# EE209_Schematic.net
KiCad netlist of a schematic drawn in Altium Designer
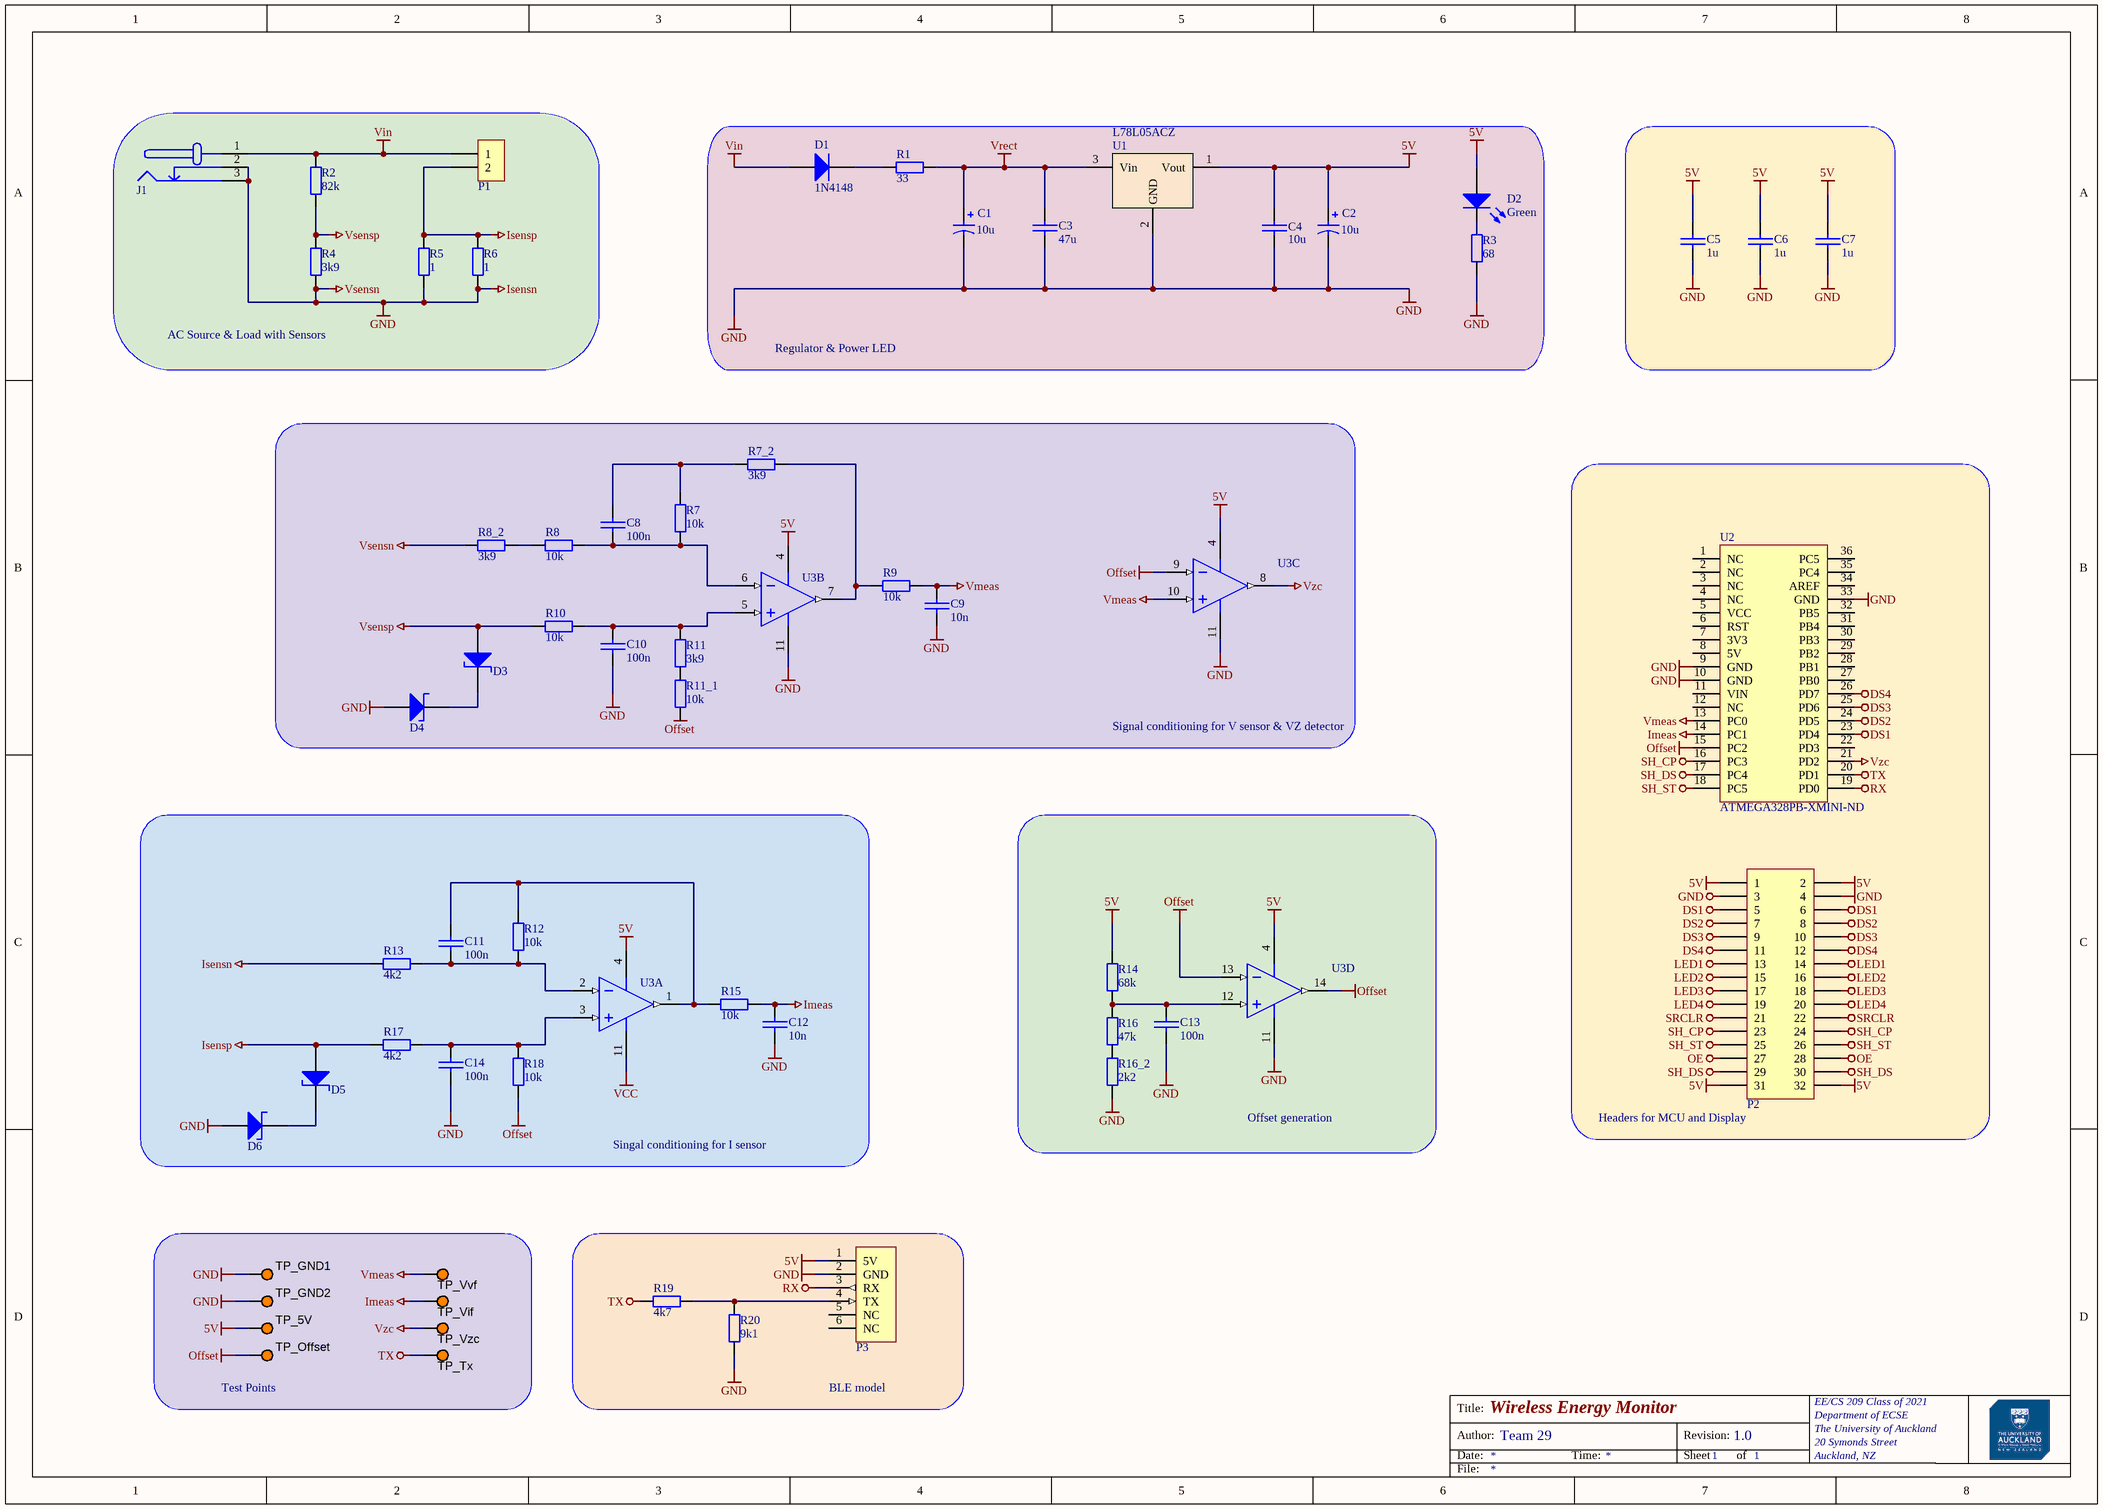
[diagram p0: EE209_Schematic.SchDoc]

(export (version "E")
  (design (tool "Eeschema 10.0.6"))
  (components
    (comp (ref "C1")
      (value "10u")
      (footprint "CAP-RAD-2.5mm Pitch")
      (description "Electrolytic capacitor with radial package, 2mm pitch and 5.2mm diameter")
      (fields (field (name "PUBLISHER") "Altium Limited"))
      (libsource (lib "EE209_Library") (part "ElecCap_TH_2P0"))
    )
    (comp (ref "C2")
      (value "10u")
      (footprint "CAP-RAD-2.5mm Pitch")
      (description "Electrolytic capacitor with radial package, 2mm pitch and 5.2mm diameter")
      (fields (field (name "PUBLISHER") "Altium Limited"))
      (libsource (lib "EE209_Library") (part "ElecCap_TH_2P0"))
    )
    (comp (ref "C3")
      (value "47u")
      (footprint "CCAP-5P0")
      (description "TH ceramic capacitor with 5mm pitch")
      (libsource (lib "EE209_Library") (part "CerCap_TH_5P0"))
    )
    (comp (ref "C4")
      (value "10u")
      (footprint "CCAP-5P0")
      (description "TH ceramic capacitor with 5mm pitch")
      (libsource (lib "EE209_Library") (part "CerCap_TH_5P0"))
    )
    (comp (ref "C5")
      (value "1u")
      (footprint "CCAP-5P0")
      (description "TH ceramic capacitor with 5mm pitch")
      (libsource (lib "EE209_Library") (part "CerCap_TH_5P0"))
    )
    (comp (ref "C6")
      (value "1u")
      (footprint "CCAP-5P0")
      (description "TH ceramic capacitor with 5mm pitch")
      (libsource (lib "EE209_Library") (part "CerCap_TH_5P0"))
    )
    (comp (ref "C7")
      (value "1u")
      (footprint "CCAP-5P0")
      (description "TH ceramic capacitor with 5mm pitch")
      (libsource (lib "EE209_Library") (part "CerCap_TH_5P0"))
    )
    (comp (ref "C8")
      (value "100n")
      (footprint "CCAP-5P0")
      (description "TH ceramic capacitor with 5mm pitch")
      (libsource (lib "EE209_Library") (part "CerCap_TH_5P0"))
    )
    (comp (ref "C9")
      (value "10n")
      (footprint "CCAP-5P0")
      (description "TH ceramic capacitor with 5mm pitch")
      (libsource (lib "EE209_Library") (part "CerCap_TH_5P0"))
    )
    (comp (ref "C10")
      (value "100n")
      (footprint "CCAP-5P0")
      (description "TH ceramic capacitor with 5mm pitch")
      (libsource (lib "EE209_Library") (part "CerCap_TH_5P0"))
    )
    (comp (ref "C11")
      (value "100n")
      (footprint "CCAP-5P0")
      (description "TH ceramic capacitor with 5mm pitch")
      (libsource (lib "EE209_Library") (part "CerCap_TH_5P0"))
    )
    (comp (ref "C12")
      (value "10n")
      (footprint "CCAP-5P0")
      (description "TH ceramic capacitor with 5mm pitch")
      (libsource (lib "EE209_Library") (part "CerCap_TH_5P0"))
    )
    (comp (ref "C13")
      (value "100n")
      (footprint "CCAP-5P0")
      (description "TH ceramic capacitor with 5mm pitch")
      (libsource (lib "EE209_Library") (part "CerCap_TH_5P0"))
    )
    (comp (ref "C14")
      (value "100n")
      (footprint "CCAP-5P0")
      (description "TH ceramic capacitor with 5mm pitch")
      (libsource (lib "EE209_Library") (part "CerCap_TH_5P0"))
    )
    (comp (ref "D1")
      (value "1N4148")
      (footprint "AXIAL-DIODE-0.4")
      (description "1N4148 100V 200mA axial diode")
      (fields
        (field (name "MANUFACTURER") "ON Semiconductor")
        (field (name "MANUFACTURER PART NUMBER") "1N4148TR")
      )
      (libsource (lib "EE209_Library") (part "1N4148_TH_4AX0"))
    )
    (comp (ref "D2")
      (value "Green")
      (footprint "LED")
      (description "Typical throughole GaAs LED with 2.54mm pitch")
      (fields (field (name "MANUFACTURER") "Generic Components") (field (name "PUBLISHER") "Altium Limited"))
      (libsource (lib "EE209_Library") (part "LED_TH_2P54"))
    )
    (comp (ref "D3")
      (value "BZX79-CXVX")
      (footprint "AXIAL-Zener-0.4")
      (description "Axial zener diode BZX79 series")
      (fields
        (field (name "MANUFACTURER") "Nexperia USA Inc.")
        (field (name "MANUFACTURER PART NUMBER") "BZX79-C4V7,143")
      )
      (libsource (lib "EE209_Library") (part "Zener_TH_4AX0"))
    )
    (comp (ref "D4")
      (value "BZX79-CXVX")
      (footprint "AXIAL-Zener-0.4")
      (description "Axial zener diode BZX79 series")
      (fields
        (field (name "MANUFACTURER") "Nexperia USA Inc.")
        (field (name "MANUFACTURER PART NUMBER") "BZX79-C4V7,143")
      )
      (libsource (lib "EE209_Library") (part "Zener_TH_4AX0"))
    )
    (comp (ref "D5")
      (value "BZX79-CXVX")
      (footprint "AXIAL-Zener-0.4")
      (description "Axial zener diode BZX79 series")
      (fields
        (field (name "MANUFACTURER") "Nexperia USA Inc.")
        (field (name "MANUFACTURER PART NUMBER") "BZX79-C4V7,143")
      )
      (libsource (lib "EE209_Library") (part "Zener_TH_4AX0"))
    )
    (comp (ref "D6")
      (value "BZX79-CXVX")
      (footprint "AXIAL-Zener-0.4")
      (description "Axial zener diode BZX79 series")
      (fields
        (field (name "MANUFACTURER") "Nexperia USA Inc.")
        (field (name "MANUFACTURER PART NUMBER") "BZX79-C4V7,143")
      )
      (libsource (lib "EE209_Library") (part "Zener_TH_4AX0"))
    )
    (comp (ref "J1")
      (value "DC barrel jack")
      (footprint "AC-Socket")
      (description "DC barrel jack connection to AC source")
      (libsource (lib "EE209_Library") (part "AC_Input"))
    )
    (comp (ref "P1")
      (value "Dual Banana Plugs")
      (footprint "Dual Banana Plug")
      (description "Dual banana plugs connection to the AC load")
      (fields (field (name "PUBLISHER") "Altium Limited"))
      (libsource (lib "EE209_Library") (part "AC_Output"))
    )
    (comp (ref "P2")
      (value "Display")
      (footprint "Display")
      (description "16-Pin Header Connecting Display")
      (libsource (lib "EE209_Library") (part "Display"))
    )
    (comp (ref "P3")
      (value "BLE Module Header")
      (footprint "HM10_HDR1X6")
      (description "2.54mm pitch 6-pin header for BLE module")
      (fields (field (name "PUBLISHER") "Altium Limited"))
      (libsource (lib "EE209_Library") (part "BLEModule_TH"))
    )
    (comp (ref "R1")
      (value "33")
      (footprint "AXIAL-0.4")
      (description "Through hole resistor")
      (fields (field (name "PUBLISHER") "Altium Limited"))
      (libsource (lib "EE209_Library") (part "Res_TH_0AX4"))
    )
    (comp (ref "R2")
      (value "82k")
      (footprint "AXIAL-0.4")
      (description "Through hole resistor")
      (fields (field (name "PUBLISHER") "Altium Limited"))
      (libsource (lib "") (part "Res_TH_0AX4_1"))
    )
    (comp (ref "R3")
      (value "68")
      (footprint "AXIAL-0.4")
      (description "Through hole resistor")
      (fields (field (name "PUBLISHER") "Altium Limited"))
      (libsource (lib "") (part "Res_TH_0AX4_1"))
    )
    (comp (ref "R4")
      (value "3k9")
      (footprint "AXIAL-0.4")
      (description "Through hole resistor")
      (fields (field (name "PUBLISHER") "Altium Limited"))
      (libsource (lib "") (part "Res_TH_0AX4_1"))
    )
    (comp (ref "R5")
      (value "1")
      (footprint "AXIAL-0.4")
      (description "Through hole resistor")
      (fields (field (name "PUBLISHER") "Altium Limited"))
      (libsource (lib "") (part "Res_TH_0AX4_1"))
    )
    (comp (ref "R6")
      (value "1")
      (footprint "AXIAL-0.4")
      (description "Through hole resistor")
      (fields (field (name "PUBLISHER") "Altium Limited"))
      (libsource (lib "") (part "Res_TH_0AX4_1"))
    )
    (comp (ref "R7")
      (value "10k")
      (footprint "AXIAL-0.4")
      (description "Through hole resistor")
      (fields (field (name "PUBLISHER") "Altium Limited"))
      (libsource (lib "") (part "Res_TH_0AX4_1"))
    )
    (comp (ref "R7_2")
      (value "3k9")
      (footprint "AXIAL-0.4")
      (description "Through hole resistor")
      (fields (field (name "PUBLISHER") "Altium Limited"))
      (libsource (lib "") (part "Res_TH_0AX4_2"))
    )
    (comp (ref "R8")
      (value "10k")
      (footprint "AXIAL-0.4")
      (description "Through hole resistor")
      (fields (field (name "PUBLISHER") "Altium Limited"))
      (libsource (lib "EE209_Library") (part "Res_TH_0AX4"))
    )
    (comp (ref "R8_2")
      (value "3k9")
      (footprint "AXIAL-0.4")
      (description "Through hole resistor")
      (fields (field (name "PUBLISHER") "Altium Limited"))
      (libsource (lib "EE209_Library") (part "Res_TH_0AX4"))
    )
    (comp (ref "R9")
      (value "10k")
      (footprint "AXIAL-0.4")
      (description "Through hole resistor")
      (fields (field (name "PUBLISHER") "Altium Limited"))
      (libsource (lib "EE209_Library") (part "Res_TH_0AX4"))
    )
    (comp (ref "R10")
      (value "10k")
      (footprint "AXIAL-0.4")
      (description "Through hole resistor")
      (fields (field (name "PUBLISHER") "Altium Limited"))
      (libsource (lib "EE209_Library") (part "Res_TH_0AX4"))
    )
    (comp (ref "R11")
      (value "3k9")
      (footprint "AXIAL-0.4")
      (description "Through hole resistor")
      (fields (field (name "PUBLISHER") "Altium Limited"))
      (libsource (lib "") (part "Res_TH_0AX4_1"))
    )
    (comp (ref "R11_1")
      (value "10k")
      (footprint "AXIAL-0.4")
      (description "Through hole resistor")
      (fields (field (name "PUBLISHER") "Altium Limited"))
      (libsource (lib "") (part "Res_TH_0AX4_1"))
    )
    (comp (ref "R12")
      (value "10k")
      (footprint "AXIAL-0.4")
      (description "Through hole resistor")
      (fields (field (name "PUBLISHER") "Altium Limited"))
      (libsource (lib "") (part "Res_TH_0AX4_1"))
    )
    (comp (ref "R13")
      (value "4k2")
      (footprint "AXIAL-0.4")
      (description "Through hole resistor")
      (fields (field (name "PUBLISHER") "Altium Limited"))
      (libsource (lib "EE209_Library") (part "Res_TH_0AX4"))
    )
    (comp (ref "R14")
      (value "68k")
      (footprint "AXIAL-0.4")
      (description "Through hole resistor")
      (fields (field (name "PUBLISHER") "Altium Limited"))
      (libsource (lib "") (part "Res_TH_0AX4_1"))
    )
    (comp (ref "R15")
      (value "10k")
      (footprint "AXIAL-0.4")
      (description "Through hole resistor")
      (fields (field (name "PUBLISHER") "Altium Limited"))
      (libsource (lib "EE209_Library") (part "Res_TH_0AX4"))
    )
    (comp (ref "R16")
      (value "47k")
      (footprint "AXIAL-0.4")
      (description "Through hole resistor")
      (fields (field (name "PUBLISHER") "Altium Limited"))
      (libsource (lib "") (part "Res_TH_0AX4_1"))
    )
    (comp (ref "R16_2")
      (value "2k2")
      (footprint "AXIAL-0.4")
      (description "Through hole resistor")
      (fields (field (name "PUBLISHER") "Altium Limited"))
      (libsource (lib "") (part "Res_TH_0AX4_1"))
    )
    (comp (ref "R17")
      (value "4k2")
      (footprint "AXIAL-0.4")
      (description "Through hole resistor")
      (fields (field (name "PUBLISHER") "Altium Limited"))
      (libsource (lib "EE209_Library") (part "Res_TH_0AX4"))
    )
    (comp (ref "R18")
      (value "10k")
      (footprint "AXIAL-0.4")
      (description "Through hole resistor")
      (fields (field (name "PUBLISHER") "Altium Limited"))
      (libsource (lib "") (part "Res_TH_0AX4_1"))
    )
    (comp (ref "R19")
      (value "4k7")
      (footprint "AXIAL-0.4")
      (description "Through hole resistor")
      (fields (field (name "PUBLISHER") "Altium Limited"))
      (libsource (lib "EE209_Library") (part "Res_TH_0AX4"))
    )
    (comp (ref "R20")
      (value "9k1")
      (footprint "AXIAL-0.4")
      (description "Through hole resistor")
      (fields (field (name "PUBLISHER") "Altium Limited"))
      (libsource (lib "") (part "Res_TH_0AX4_1"))
    )
    (comp (ref "TP_5V")
      (value "5003")
      (footprint "TP_TH")
      (description "Test Point, Orange, 1-Pin THD, RoHS")
      (libsource (lib "EE209_Library") (part "TestPoint"))
    )
    (comp (ref "TP_GND1")
      (value "5003")
      (footprint "TP_TH")
      (description "Test Point, Orange, 1-Pin THD, RoHS")
      (libsource (lib "EE209_Library") (part "TestPoint"))
    )
    (comp (ref "TP_GND2")
      (value "5003")
      (footprint "TP_TH")
      (description "Test Point, Orange, 1-Pin THD, RoHS")
      (libsource (lib "EE209_Library") (part "TestPoint"))
    )
    (comp (ref "TP_Offset")
      (value "5003")
      (footprint "TP_TH")
      (description "Test Point, Orange, 1-Pin THD, RoHS")
      (libsource (lib "EE209_Library") (part "TestPoint"))
    )
    (comp (ref "TP_Tx")
      (value "5003")
      (footprint "TP_TH")
      (description "Test Point, Orange, 1-Pin THD, RoHS")
      (libsource (lib "EE209_Library") (part "TestPoint"))
    )
    (comp (ref "TP_Vif")
      (value "5003")
      (footprint "TP_TH")
      (description "Test Point, Orange, 1-Pin THD, RoHS")
      (libsource (lib "EE209_Library") (part "TestPoint"))
    )
    (comp (ref "TP_Vvf")
      (value "5003")
      (footprint "TP_TH")
      (description "Test Point, Orange, 1-Pin THD, RoHS")
      (libsource (lib "EE209_Library") (part "TestPoint"))
    )
    (comp (ref "TP_Vzc")
      (value "5003")
      (footprint "TP_TH")
      (description "Test Point, Orange, 1-Pin THD, RoHS")
      (libsource (lib "EE209_Library") (part "TestPoint"))
    )
    (comp (ref "U1")
      (value "L78L05ACZ")
      (footprint "TO-92")
      (description "Voltage Regulator 5V")
      (fields
        (field (name "MANUFACTURER") "ON Semiconductor")
        (field (name "MANUFACTURER PART NUMBER") "LM78L05ACZX")
      )
      (libsource (lib "EE209_Library") (part "L78L05_TH_TO92"))
    )
    (comp (ref "U2")
      (value "ATmega328PB Xplained Mini Header")
      (footprint "ATmeg328P Xplained")
      (description "Dual 18-pin headers connecting to ATmega328PB Xplained Mini")
      (fields
        (field (name "MANUFACTURER") "Microchip Technology")
        (field (name "MANUFACTURER PART NUMBER") "ATMEGA328PB-XMINI")
        (field (name "SUPPLIER PART NUMBER 1") "ATMEGA328PB-XMINI-ND")
      )
      (libsource (lib "EE209_Library") (part "ATmega328PBXplained_TH"))
    )
    (comp (ref "U3")
      (value "LM324")
      (footprint "DIP-14")
      (description "IC OPAMP GP 14DIP")
      (fields
        (field (name "MANUFACTURER") "ON Semiconductor")
        (field (name "MANUFACTURER PART NUMBER") "LM324N")
      )
      (libsource (lib "EE209_Library") (part "LM324N_TH_DIP16"))
    )
  )
  (nets
    (net (code "1") (name "5V") (class "Default")
      (node (ref "C2") (pin "1") (pinfunction "1_1") (pintype "passive"))
      (node (ref "C4") (pin "1") (pinfunction "1_1") (pintype "passive"))
      (node (ref "C5") (pin "1") (pinfunction "1_1") (pintype "passive"))
      (node (ref "C6") (pin "1") (pinfunction "1_1") (pintype "passive"))
      (node (ref "C7") (pin "1") (pinfunction "1_1") (pintype "passive"))
      (node (ref "D2") (pin "1") (pinfunction "A_1") (pintype "passive"))
      (node (ref "P2") (pin "1") (pinfunction "1_1") (pintype "passive"))
      (node (ref "P2") (pin "2") (pinfunction "2_2") (pintype "passive"))
      (node (ref "P2") (pin "31") (pinfunction "31_31") (pintype "passive"))
      (node (ref "P2") (pin "32") (pinfunction "32_32") (pintype "passive"))
      (node (ref "P3") (pin "1") (pinfunction "5V_1") (pintype "passive"))
      (node (ref "R14") (pin "2") (pinfunction "2_2") (pintype "passive"))
      (node (ref "TP_5V") (pin "1") (pinfunction "1_1") (pintype "passive"))
      (node (ref "U1") (pin "1") (pinfunction "Vout_1") (pintype "passive"))
      (node (ref "U3") (pin "4") (pinfunction "VDD_4") (pintype "power_in"))
    )
    (net (code "2") (name "DS1") (class "Default")
      (node (ref "P2") (pin "5") (pinfunction "5_5") (pintype "passive"))
      (node (ref "P2") (pin "6") (pinfunction "6_6") (pintype "passive"))
      (node (ref "U2") (pin "23") (pinfunction "PD4_23") (pintype "passive"))
    )
    (net (code "3") (name "DS2") (class "Default")
      (node (ref "P2") (pin "7") (pinfunction "7_7") (pintype "passive"))
      (node (ref "P2") (pin "8") (pinfunction "8_8") (pintype "passive"))
      (node (ref "U2") (pin "24") (pinfunction "PD5_24") (pintype "passive"))
    )
    (net (code "4") (name "DS3") (class "Default")
      (node (ref "P2") (pin "10") (pinfunction "10_10") (pintype "passive"))
      (node (ref "P2") (pin "9") (pinfunction "9_9") (pintype "passive"))
      (node (ref "U2") (pin "25") (pinfunction "PD6_25") (pintype "passive"))
    )
    (net (code "5") (name "DS4") (class "Default")
      (node (ref "P2") (pin "11") (pinfunction "11_11") (pintype "passive"))
      (node (ref "P2") (pin "12") (pinfunction "12_12") (pintype "passive"))
      (node (ref "U2") (pin "26") (pinfunction "PD7_26") (pintype "passive"))
    )
    (net (code "6") (name "GND") (class "Default")
      (node (ref "C1") (pin "2") (pinfunction "2_2") (pintype "passive"))
      (node (ref "C10") (pin "2") (pinfunction "2_2") (pintype "passive"))
      (node (ref "C12") (pin "2") (pinfunction "2_2") (pintype "passive"))
      (node (ref "C13") (pin "2") (pinfunction "2_2") (pintype "passive"))
      (node (ref "C14") (pin "2") (pinfunction "2_2") (pintype "passive"))
      (node (ref "C2") (pin "2") (pinfunction "2_2") (pintype "passive"))
      (node (ref "C3") (pin "2") (pinfunction "2_2") (pintype "passive"))
      (node (ref "C4") (pin "2") (pinfunction "2_2") (pintype "passive"))
      (node (ref "C5") (pin "2") (pinfunction "2_2") (pintype "passive"))
      (node (ref "C6") (pin "2") (pinfunction "2_2") (pintype "passive"))
      (node (ref "C7") (pin "2") (pinfunction "2_2") (pintype "passive"))
      (node (ref "C9") (pin "2") (pinfunction "2_2") (pintype "passive"))
      (node (ref "D4") (pin "1") (pinfunction "A_1") (pintype "passive"))
      (node (ref "D6") (pin "1") (pinfunction "A_1") (pintype "passive"))
      (node (ref "J1") (pin "2") (pinfunction "GND_ALT_2") (pintype "power_in"))
      (node (ref "J1") (pin "3") (pinfunction "GND_3") (pintype "power_in"))
      (node (ref "P2") (pin "3") (pinfunction "3_3") (pintype "passive"))
      (node (ref "P2") (pin "4") (pinfunction "4_4") (pintype "passive"))
      (node (ref "P3") (pin "2") (pinfunction "GND_2") (pintype "passive"))
      (node (ref "R13") (pin "1") (pinfunction "1_1") (pintype "passive"))
      (node (ref "R16_2") (pin "1") (pinfunction "1_1") (pintype "passive"))
      (node (ref "R20") (pin "1") (pinfunction "1_1") (pintype "passive"))
      (node (ref "R3") (pin "1") (pinfunction "1_1") (pintype "passive"))
      (node (ref "R4") (pin "1") (pinfunction "1_1") (pintype "passive"))
      (node (ref "R5") (pin "1") (pinfunction "1_1") (pintype "passive"))
      (node (ref "R6") (pin "1") (pinfunction "1_1") (pintype "passive"))
      (node (ref "R8_2") (pin "1") (pinfunction "1_1") (pintype "passive"))
      (node (ref "TP_GND1") (pin "1") (pinfunction "1_1") (pintype "passive"))
      (node (ref "TP_GND2") (pin "1") (pinfunction "1_1") (pintype "passive"))
      (node (ref "U1") (pin "2") (pinfunction "GND_2") (pintype "passive"))
      (node (ref "U2") (pin "10") (pinfunction "GND_10") (pintype "power_in"))
      (node (ref "U2") (pin "33") (pinfunction "GND_33") (pintype "passive"))
      (node (ref "U2") (pin "9") (pinfunction "GND_9") (pintype "power_in"))
      (node (ref "U3") (pin "11") (pinfunction "VSS_11") (pintype "power_in"))
    )
    (net (code "7") (name "Imeas") (class "Default")
      (node (ref "C12") (pin "1") (pinfunction "1_1") (pintype "passive"))
      (node (ref "R15") (pin "2") (pinfunction "2_2") (pintype "passive"))
      (node (ref "TP_Vif") (pin "1") (pinfunction "1_1") (pintype "passive"))
      (node (ref "U2") (pin "14") (pinfunction "PC1_14") (pintype "passive"))
    )
    (net (code "8") (name "Isensp") (class "Default")
      (node (ref "D5") (pin "1") (pinfunction "A_1") (pintype "passive"))
      (node (ref "P1") (pin "2") (pinfunction "2_2") (pintype "passive"))
      (node (ref "R17") (pin "1") (pinfunction "1_1") (pintype "passive"))
      (node (ref "R5") (pin "2") (pinfunction "2_2") (pintype "passive"))
      (node (ref "R6") (pin "2") (pinfunction "2_2") (pintype "passive"))
    )
    (net (code "9") (name "LED1") (class "Default")
      (node (ref "P2") (pin "13") (pinfunction "13_13") (pintype "passive"))
      (node (ref "P2") (pin "14") (pinfunction "14_14") (pintype "passive"))
    )
    (net (code "10") (name "LED2") (class "Default")
      (node (ref "P2") (pin "15") (pinfunction "15_15") (pintype "passive"))
      (node (ref "P2") (pin "16") (pinfunction "16_16") (pintype "passive"))
    )
    (net (code "11") (name "LED3") (class "Default")
      (node (ref "P2") (pin "17") (pinfunction "17_17") (pintype "passive"))
      (node (ref "P2") (pin "18") (pinfunction "18_18") (pintype "passive"))
    )
    (net (code "12") (name "LED4") (class "Default")
      (node (ref "P2") (pin "19") (pinfunction "19_19") (pintype "passive"))
      (node (ref "P2") (pin "20") (pinfunction "20_20") (pintype "passive"))
    )
    (net (code "13") (name "Net-(C8-Pad1)") (class "Default")
      (node (ref "C8") (pin "1") (pinfunction "1_1") (pintype "passive"))
      (node (ref "R7") (pin "2") (pinfunction "2_2") (pintype "passive"))
      (node (ref "R7_2") (pin "2") (pinfunction "2_2") (pintype "passive"))
    )
    (net (code "14") (name "Net-(D1-K)") (class "Default")
      (node (ref "D1") (pin "2") (pinfunction "K_2") (pintype "passive"))
      (node (ref "R1") (pin "1") (pinfunction "1_1") (pintype "passive"))
    )
    (net (code "15") (name "Net-(D2-K)") (class "Default")
      (node (ref "D2") (pin "2") (pinfunction "K_2") (pintype "passive"))
      (node (ref "R3") (pin "2") (pinfunction "2_2") (pintype "passive"))
    )
    (net (code "16") (name "Net-(D3-K)") (class "Default")
      (node (ref "D3") (pin "2") (pinfunction "K_2") (pintype "passive"))
      (node (ref "D4") (pin "2") (pinfunction "K_2") (pintype "passive"))
    )
    (net (code "17") (name "Net-(D5-K)") (class "Default")
      (node (ref "D5") (pin "2") (pinfunction "K_2") (pintype "passive"))
      (node (ref "D6") (pin "2") (pinfunction "K_2") (pintype "passive"))
    )
    (net (code "18") (name "Net-(P3-TX)") (class "Default")
      (node (ref "P3") (pin "4") (pinfunction "TX_4") (pintype "input"))
      (node (ref "R19") (pin "2") (pinfunction "2_2") (pintype "passive"))
      (node (ref "R20") (pin "2") (pinfunction "2_2") (pintype "passive"))
    )
    (net (code "19") (name "Net-(R8-Pad1)") (class "Default")
      (node (ref "R8") (pin "1") (pinfunction "1_1") (pintype "passive"))
      (node (ref "R8_2") (pin "2") (pinfunction "2_2") (pintype "passive"))
    )
    (net (code "20") (name "Net-(U3A-VINA+)") (class "Default")
      (node (ref "C14") (pin "1") (pinfunction "1_1") (pintype "passive"))
      (node (ref "R17") (pin "2") (pinfunction "2_2") (pintype "passive"))
      (node (ref "R18") (pin "2") (pinfunction "2_2") (pintype "passive"))
      (node (ref "U3") (pin "3") (pinfunction "VINA+_3") (pintype "input"))
    )
    (net (code "21") (name "Net-(U3A-VINA-)") (class "Default")
      (node (ref "C11") (pin "2") (pinfunction "2_2") (pintype "passive"))
      (node (ref "R12") (pin "1") (pinfunction "1_1") (pintype "passive"))
      (node (ref "R13") (pin "2") (pinfunction "2_2") (pintype "passive"))
      (node (ref "U3") (pin "2") (pinfunction "VINA-_2") (pintype "input"))
    )
    (net (code "22") (name "Net-(U3A-VOUTA)") (class "Default")
      (node (ref "C11") (pin "1") (pinfunction "1_1") (pintype "passive"))
      (node (ref "R12") (pin "2") (pinfunction "2_2") (pintype "passive"))
      (node (ref "R15") (pin "1") (pinfunction "1_1") (pintype "passive"))
      (node (ref "U3") (pin "1") (pinfunction "VOUTA_1") (pintype "output"))
    )
    (net (code "23") (name "Net-(U3B-VINB+)") (class "Default")
      (node (ref "C10") (pin "1") (pinfunction "1_1") (pintype "passive"))
      (node (ref "R10") (pin "2") (pinfunction "2_2") (pintype "passive"))
      (node (ref "R11") (pin "2") (pinfunction "2_2") (pintype "passive"))
      (node (ref "U3") (pin "5") (pinfunction "VINB+_5") (pintype "input"))
    )
    (net (code "24") (name "Net-(U3B-VINB-)") (class "Default")
      (node (ref "C8") (pin "2") (pinfunction "2_2") (pintype "passive"))
      (node (ref "R7") (pin "1") (pinfunction "1_1") (pintype "passive"))
      (node (ref "R8") (pin "2") (pinfunction "2_2") (pintype "passive"))
      (node (ref "U3") (pin "6") (pinfunction "VINB-_6") (pintype "input"))
    )
    (net (code "25") (name "Net-(U3B-VOUTB)") (class "Default")
      (node (ref "R7_2") (pin "1") (pinfunction "1_1") (pintype "passive"))
      (node (ref "R9") (pin "1") (pinfunction "1_1") (pintype "passive"))
      (node (ref "U3") (pin "7") (pinfunction "VOUTB_7") (pintype "output"))
    )
    (net (code "26") (name "Net-(U3D-VIND+)") (class "Default")
      (node (ref "C13") (pin "1") (pinfunction "1_1") (pintype "passive"))
      (node (ref "R14") (pin "1") (pinfunction "1_1") (pintype "passive"))
      (node (ref "R16") (pin "2") (pinfunction "2_2") (pintype "passive"))
      (node (ref "U3") (pin "12") (pinfunction "VIND+_12") (pintype "input"))
    )
    (net (code "27") (name "OE") (class "Default")
      (node (ref "P2") (pin "27") (pinfunction "27_27") (pintype "passive"))
      (node (ref "P2") (pin "28") (pinfunction "28_28") (pintype "passive"))
    )
    (net (code "28") (name "Offset") (class "Default")
      (node (ref "R18") (pin "1") (pinfunction "1_1") (pintype "passive"))
      (node (ref "TP_Offset") (pin "1") (pinfunction "1_1") (pintype "passive"))
      (node (ref "U2") (pin "15") (pinfunction "PC2_15") (pintype "passive"))
      (node (ref "U3") (pin "13") (pinfunction "VIND-_13") (pintype "input"))
      (node (ref "U3") (pin "14") (pinfunction "VOUTD_14") (pintype "output"))
      (node (ref "U3") (pin "9") (pinfunction "VINC-_9") (pintype "input"))
    )
    (net (code "29") (name "RX") (class "Default")
      (node (ref "P3") (pin "3") (pinfunction "RX_3") (pintype "output"))
      (node (ref "U2") (pin "19") (pinfunction "PD0_19") (pintype "passive"))
    )
    (net (code "30") (name "SH_CP") (class "Default")
      (node (ref "P2") (pin "23") (pinfunction "23_23") (pintype "passive"))
      (node (ref "P2") (pin "24") (pinfunction "24_24") (pintype "passive"))
      (node (ref "U2") (pin "16") (pinfunction "PC3_16") (pintype "passive"))
    )
    (net (code "31") (name "SH_DS") (class "Default")
      (node (ref "P2") (pin "29") (pinfunction "29_29") (pintype "passive"))
      (node (ref "P2") (pin "30") (pinfunction "30_30") (pintype "passive"))
      (node (ref "U2") (pin "17") (pinfunction "PC4_17") (pintype "passive"))
    )
    (net (code "32") (name "SH_ST") (class "Default")
      (node (ref "P2") (pin "25") (pinfunction "25_25") (pintype "passive"))
      (node (ref "P2") (pin "26") (pinfunction "26_26") (pintype "passive"))
      (node (ref "U2") (pin "18") (pinfunction "PC5_18") (pintype "passive"))
    )
    (net (code "33") (name "SRCLR") (class "Default")
      (node (ref "P2") (pin "21") (pinfunction "21_21") (pintype "passive"))
      (node (ref "P2") (pin "22") (pinfunction "22_22") (pintype "passive"))
    )
    (net (code "34") (name "TX") (class "Default")
      (node (ref "R19") (pin "1") (pinfunction "1_1") (pintype "passive"))
      (node (ref "TP_Tx") (pin "1") (pinfunction "1_1") (pintype "passive"))
      (node (ref "U2") (pin "20") (pinfunction "PD1_20") (pintype "passive"))
    )
    (net (code "35") (name "VCC") (class "Default")
      (node (ref "U3") (pin "11") (pinfunction "VSS_11") (pintype "power_in"))
    )
    (net (code "36") (name "Vin") (class "Default")
      (node (ref "D1") (pin "1") (pinfunction "A_1") (pintype "passive"))
      (node (ref "J1") (pin "1") (pinfunction "VCC_1") (pintype "power_in"))
      (node (ref "P1") (pin "1") (pinfunction "1_1") (pintype "passive"))
      (node (ref "R2") (pin "2") (pinfunction "2_2") (pintype "passive"))
    )
    (net (code "37") (name "Vmeas") (class "Default")
      (node (ref "C9") (pin "1") (pinfunction "1_1") (pintype "passive"))
      (node (ref "R9") (pin "2") (pinfunction "2_2") (pintype "passive"))
      (node (ref "TP_Vvf") (pin "1") (pinfunction "1_1") (pintype "passive"))
      (node (ref "U2") (pin "13") (pinfunction "PC0_13") (pintype "passive"))
      (node (ref "U3") (pin "10") (pinfunction "VINC+_10") (pintype "input"))
    )
    (net (code "38") (name "Vrect") (class "Default")
      (node (ref "C1") (pin "1") (pinfunction "1_1") (pintype "passive"))
      (node (ref "C3") (pin "1") (pinfunction "1_1") (pintype "passive"))
      (node (ref "R1") (pin "2") (pinfunction "2_2") (pintype "passive"))
      (node (ref "U1") (pin "3") (pinfunction "Vin_3") (pintype "passive"))
    )
    (net (code "39") (name "Vsensp") (class "Default")
      (node (ref "D3") (pin "1") (pinfunction "A_1") (pintype "passive"))
      (node (ref "R10") (pin "1") (pinfunction "1_1") (pintype "passive"))
      (node (ref "R2") (pin "1") (pinfunction "1_1") (pintype "passive"))
      (node (ref "R4") (pin "2") (pinfunction "2_2") (pintype "passive"))
    )
    (net (code "40") (name "Vzc") (class "Default")
      (node (ref "TP_Vzc") (pin "1") (pinfunction "1_1") (pintype "passive"))
      (node (ref "U2") (pin "21") (pinfunction "PD2_21") (pintype "passive"))
      (node (ref "U3") (pin "8") (pinfunction "VOUTC_8") (pintype "output"))
    )
    (net (code "41") (name "unconnected-(P3-NC-Pad5)") (class "Default")
      (node (ref "P3") (pin "5") (pinfunction "NC_5") (pintype "passive"))
    )
    (net (code "42") (name "unconnected-(P3-NC-Pad6)") (class "Default")
      (node (ref "P3") (pin "6") (pinfunction "NC_6") (pintype "passive"))
    )
    (net (code "43") (name "unconnected-(R11-Pad1)") (class "Default")
      (node (ref "R11") (pin "1") (pinfunction "1_1") (pintype "passive"))
    )
    (net (code "44") (name "unconnected-(R11_1-Pad1)") (class "Default")
      (node (ref "R11_1") (pin "1") (pinfunction "1_1") (pintype "passive"))
    )
    (net (code "45") (name "unconnected-(R11_1-Pad2)") (class "Default")
      (node (ref "R11_1") (pin "2") (pinfunction "2_2") (pintype "passive"))
    )
    (net (code "46") (name "unconnected-(R16-Pad1)") (class "Default")
      (node (ref "R16") (pin "1") (pinfunction "1_1") (pintype "passive"))
    )
    (net (code "47") (name "unconnected-(R16_2-Pad2)") (class "Default")
      (node (ref "R16_2") (pin "2") (pinfunction "2_2") (pintype "passive"))
    )
    (net (code "48") (name "unconnected-(U2-3V3-Pad7)") (class "Default")
      (node (ref "U2") (pin "7") (pinfunction "3V3_7") (pintype "passive"))
    )
    (net (code "49") (name "unconnected-(U2-5V-Pad8)") (class "Default")
      (node (ref "U2") (pin "8") (pinfunction "5V_8") (pintype "power_in"))
    )
    (net (code "50") (name "unconnected-(U2-AREF-Pad34)") (class "Default")
      (node (ref "U2") (pin "34") (pinfunction "AREF_34") (pintype "passive"))
    )
    (net (code "51") (name "unconnected-(U2-NC-Pad1)") (class "Default")
      (node (ref "U2") (pin "1") (pinfunction "NC_1") (pintype "passive"))
    )
    (net (code "52") (name "unconnected-(U2-NC-Pad2)") (class "Default")
      (node (ref "U2") (pin "2") (pinfunction "NC_2") (pintype "passive"))
    )
    (net (code "53") (name "unconnected-(U2-NC-Pad3)") (class "Default")
      (node (ref "U2") (pin "3") (pinfunction "NC_3") (pintype "passive"))
    )
    (net (code "54") (name "unconnected-(U2-NC-Pad4)") (class "Default")
      (node (ref "U2") (pin "4") (pinfunction "NC_4") (pintype "passive"))
    )
    (net (code "55") (name "unconnected-(U2-NC-Pad12)") (class "Default")
      (node (ref "U2") (pin "12") (pinfunction "NC_12") (pintype "passive"))
    )
    (net (code "56") (name "unconnected-(U2-PB0-Pad27)") (class "Default")
      (node (ref "U2") (pin "27") (pinfunction "PB0_27") (pintype "passive"))
    )
    (net (code "57") (name "unconnected-(U2-PB1-Pad28)") (class "Default")
      (node (ref "U2") (pin "28") (pinfunction "PB1_28") (pintype "passive"))
    )
    (net (code "58") (name "unconnected-(U2-PB2-Pad29)") (class "Default")
      (node (ref "U2") (pin "29") (pinfunction "PB2_29") (pintype "passive"))
    )
    (net (code "59") (name "unconnected-(U2-PB3-Pad30)") (class "Default")
      (node (ref "U2") (pin "30") (pinfunction "PB3_30") (pintype "passive"))
    )
    (net (code "60") (name "unconnected-(U2-PB4-Pad31)") (class "Default")
      (node (ref "U2") (pin "31") (pinfunction "PB4_31") (pintype "passive"))
    )
    (net (code "61") (name "unconnected-(U2-PB5-Pad32)") (class "Default")
      (node (ref "U2") (pin "32") (pinfunction "PB5_32") (pintype "passive"))
    )
    (net (code "62") (name "unconnected-(U2-PC4-Pad35)") (class "Default")
      (node (ref "U2") (pin "35") (pinfunction "PC4_35") (pintype "passive"))
    )
    (net (code "63") (name "unconnected-(U2-PC5-Pad36)") (class "Default")
      (node (ref "U2") (pin "36") (pinfunction "PC5_36") (pintype "passive"))
    )
    (net (code "64") (name "unconnected-(U2-PD3-Pad22)") (class "Default")
      (node (ref "U2") (pin "22") (pinfunction "PD3_22") (pintype "passive"))
    )
    (net (code "65") (name "unconnected-(U2-RST-Pad6)") (class "Default")
      (node (ref "U2") (pin "6") (pinfunction "RST_6") (pintype "passive"))
    )
    (net (code "66") (name "unconnected-(U2-VCC-Pad5)") (class "Default")
      (node (ref "U2") (pin "5") (pinfunction "VCC_5") (pintype "power_in"))
    )
    (net (code "67") (name "unconnected-(U2-VIN-Pad11)") (class "Default")
      (node (ref "U2") (pin "11") (pinfunction "VIN_11") (pintype "power_in"))
    )
  )
)
